# pcb6.net
KiCad netlist of a schematic drawn in EAGLE
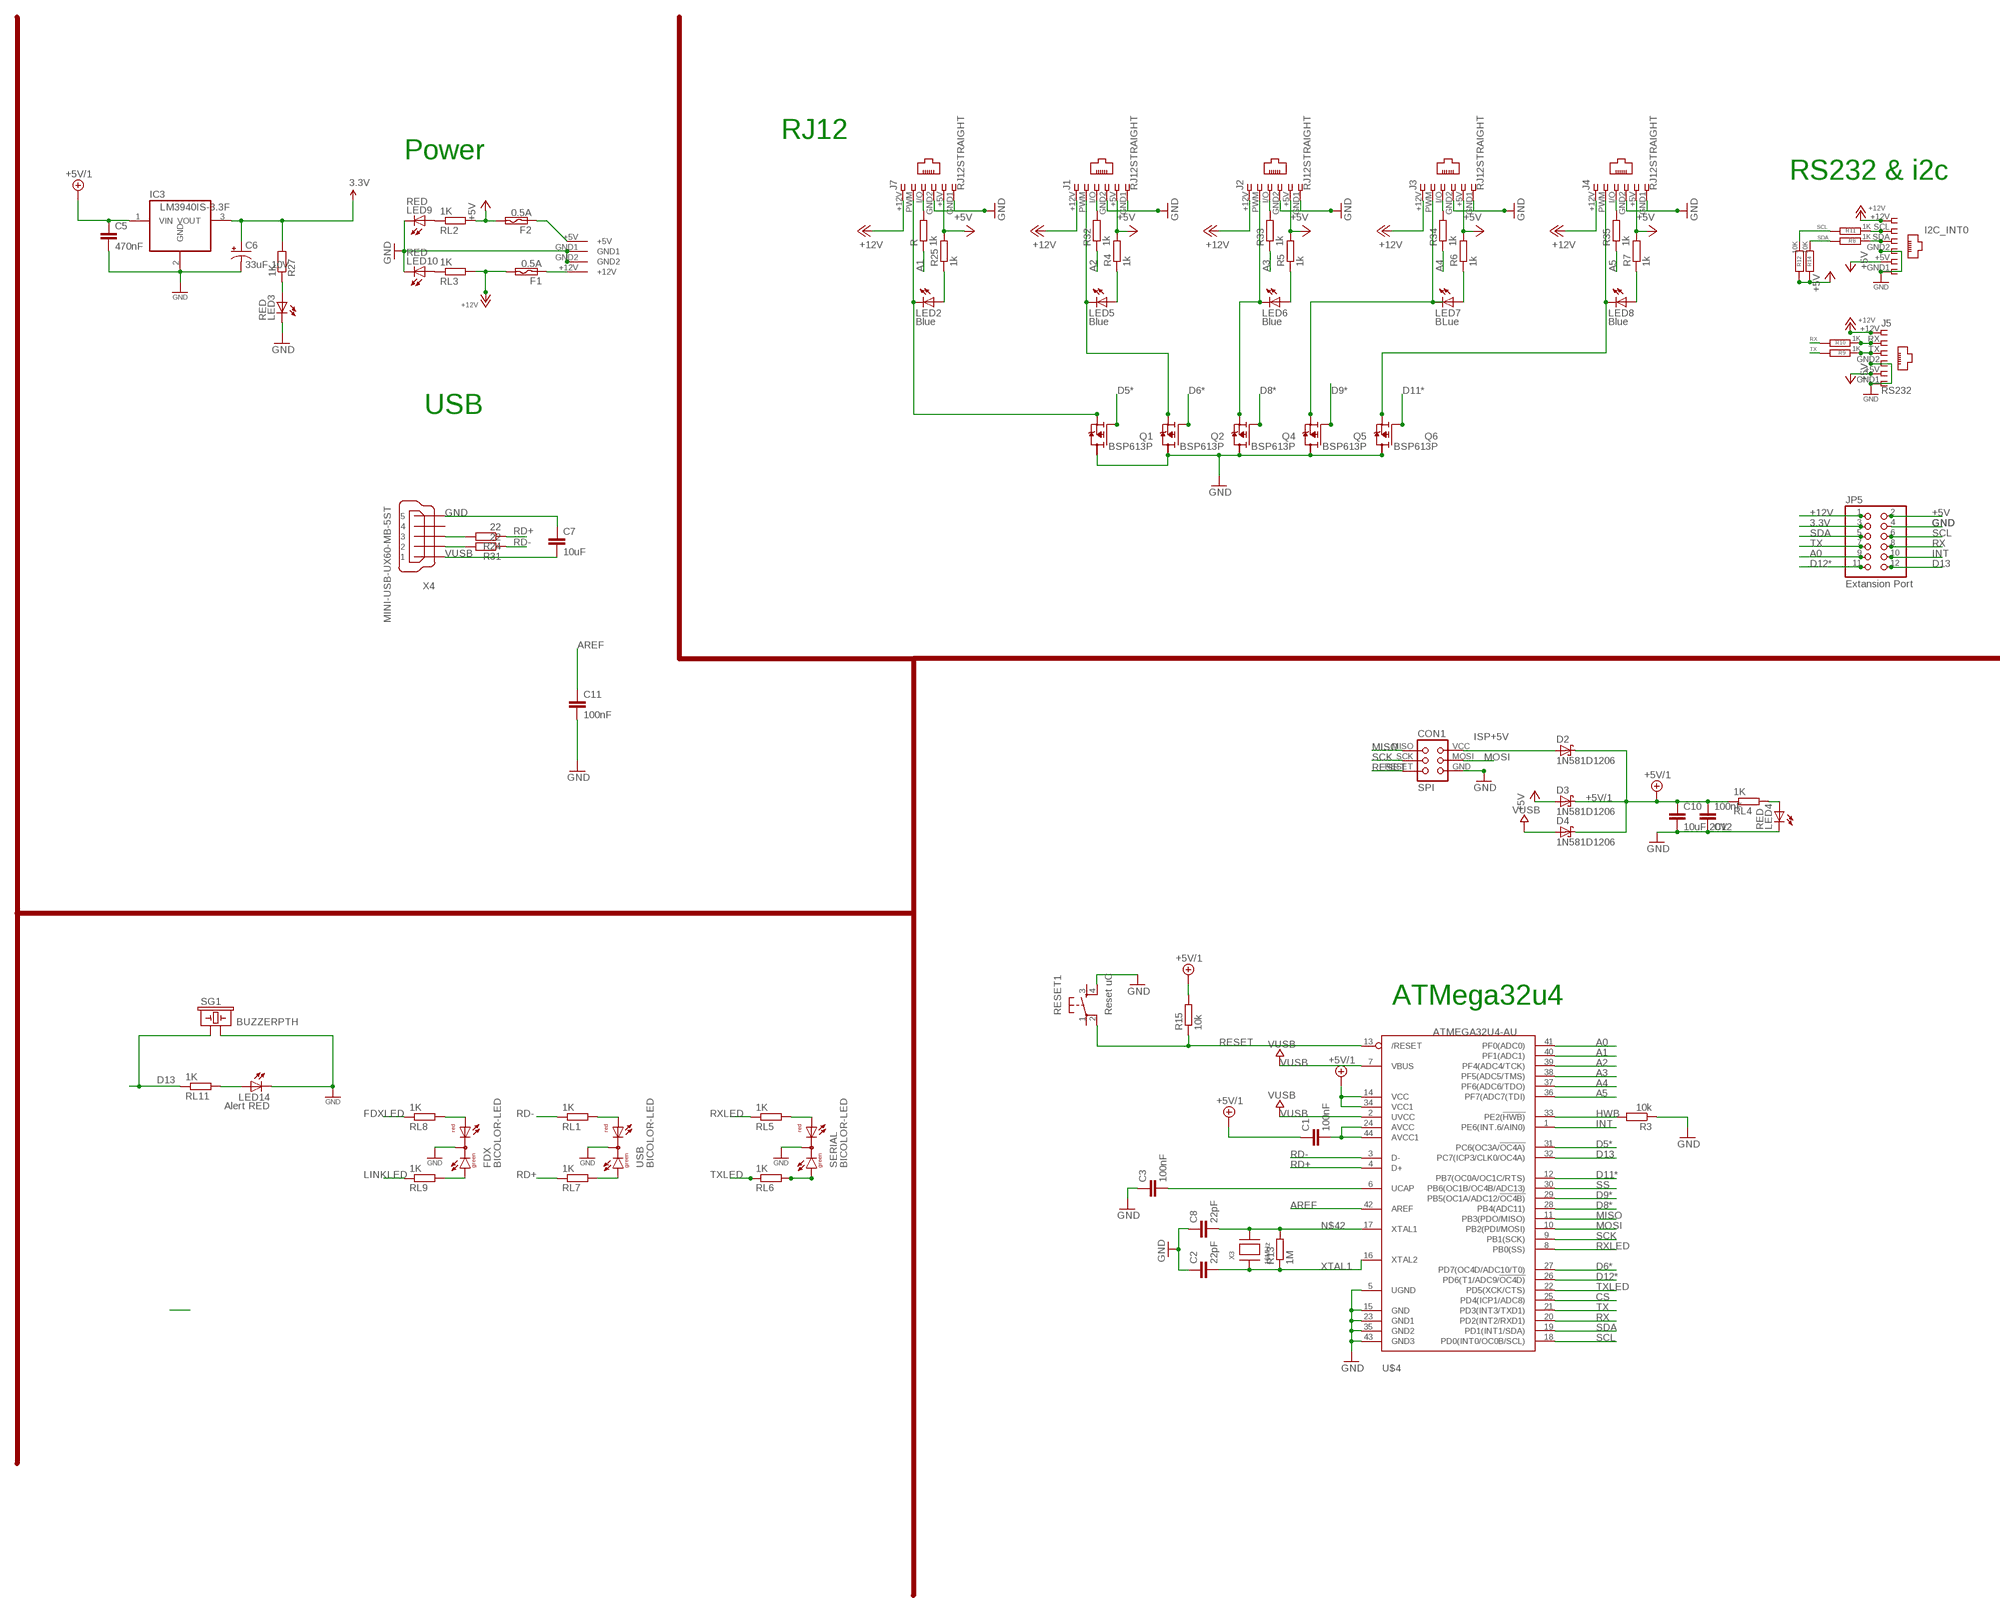
[diagram p0: schematic, sheet 1, part 1 of 2]
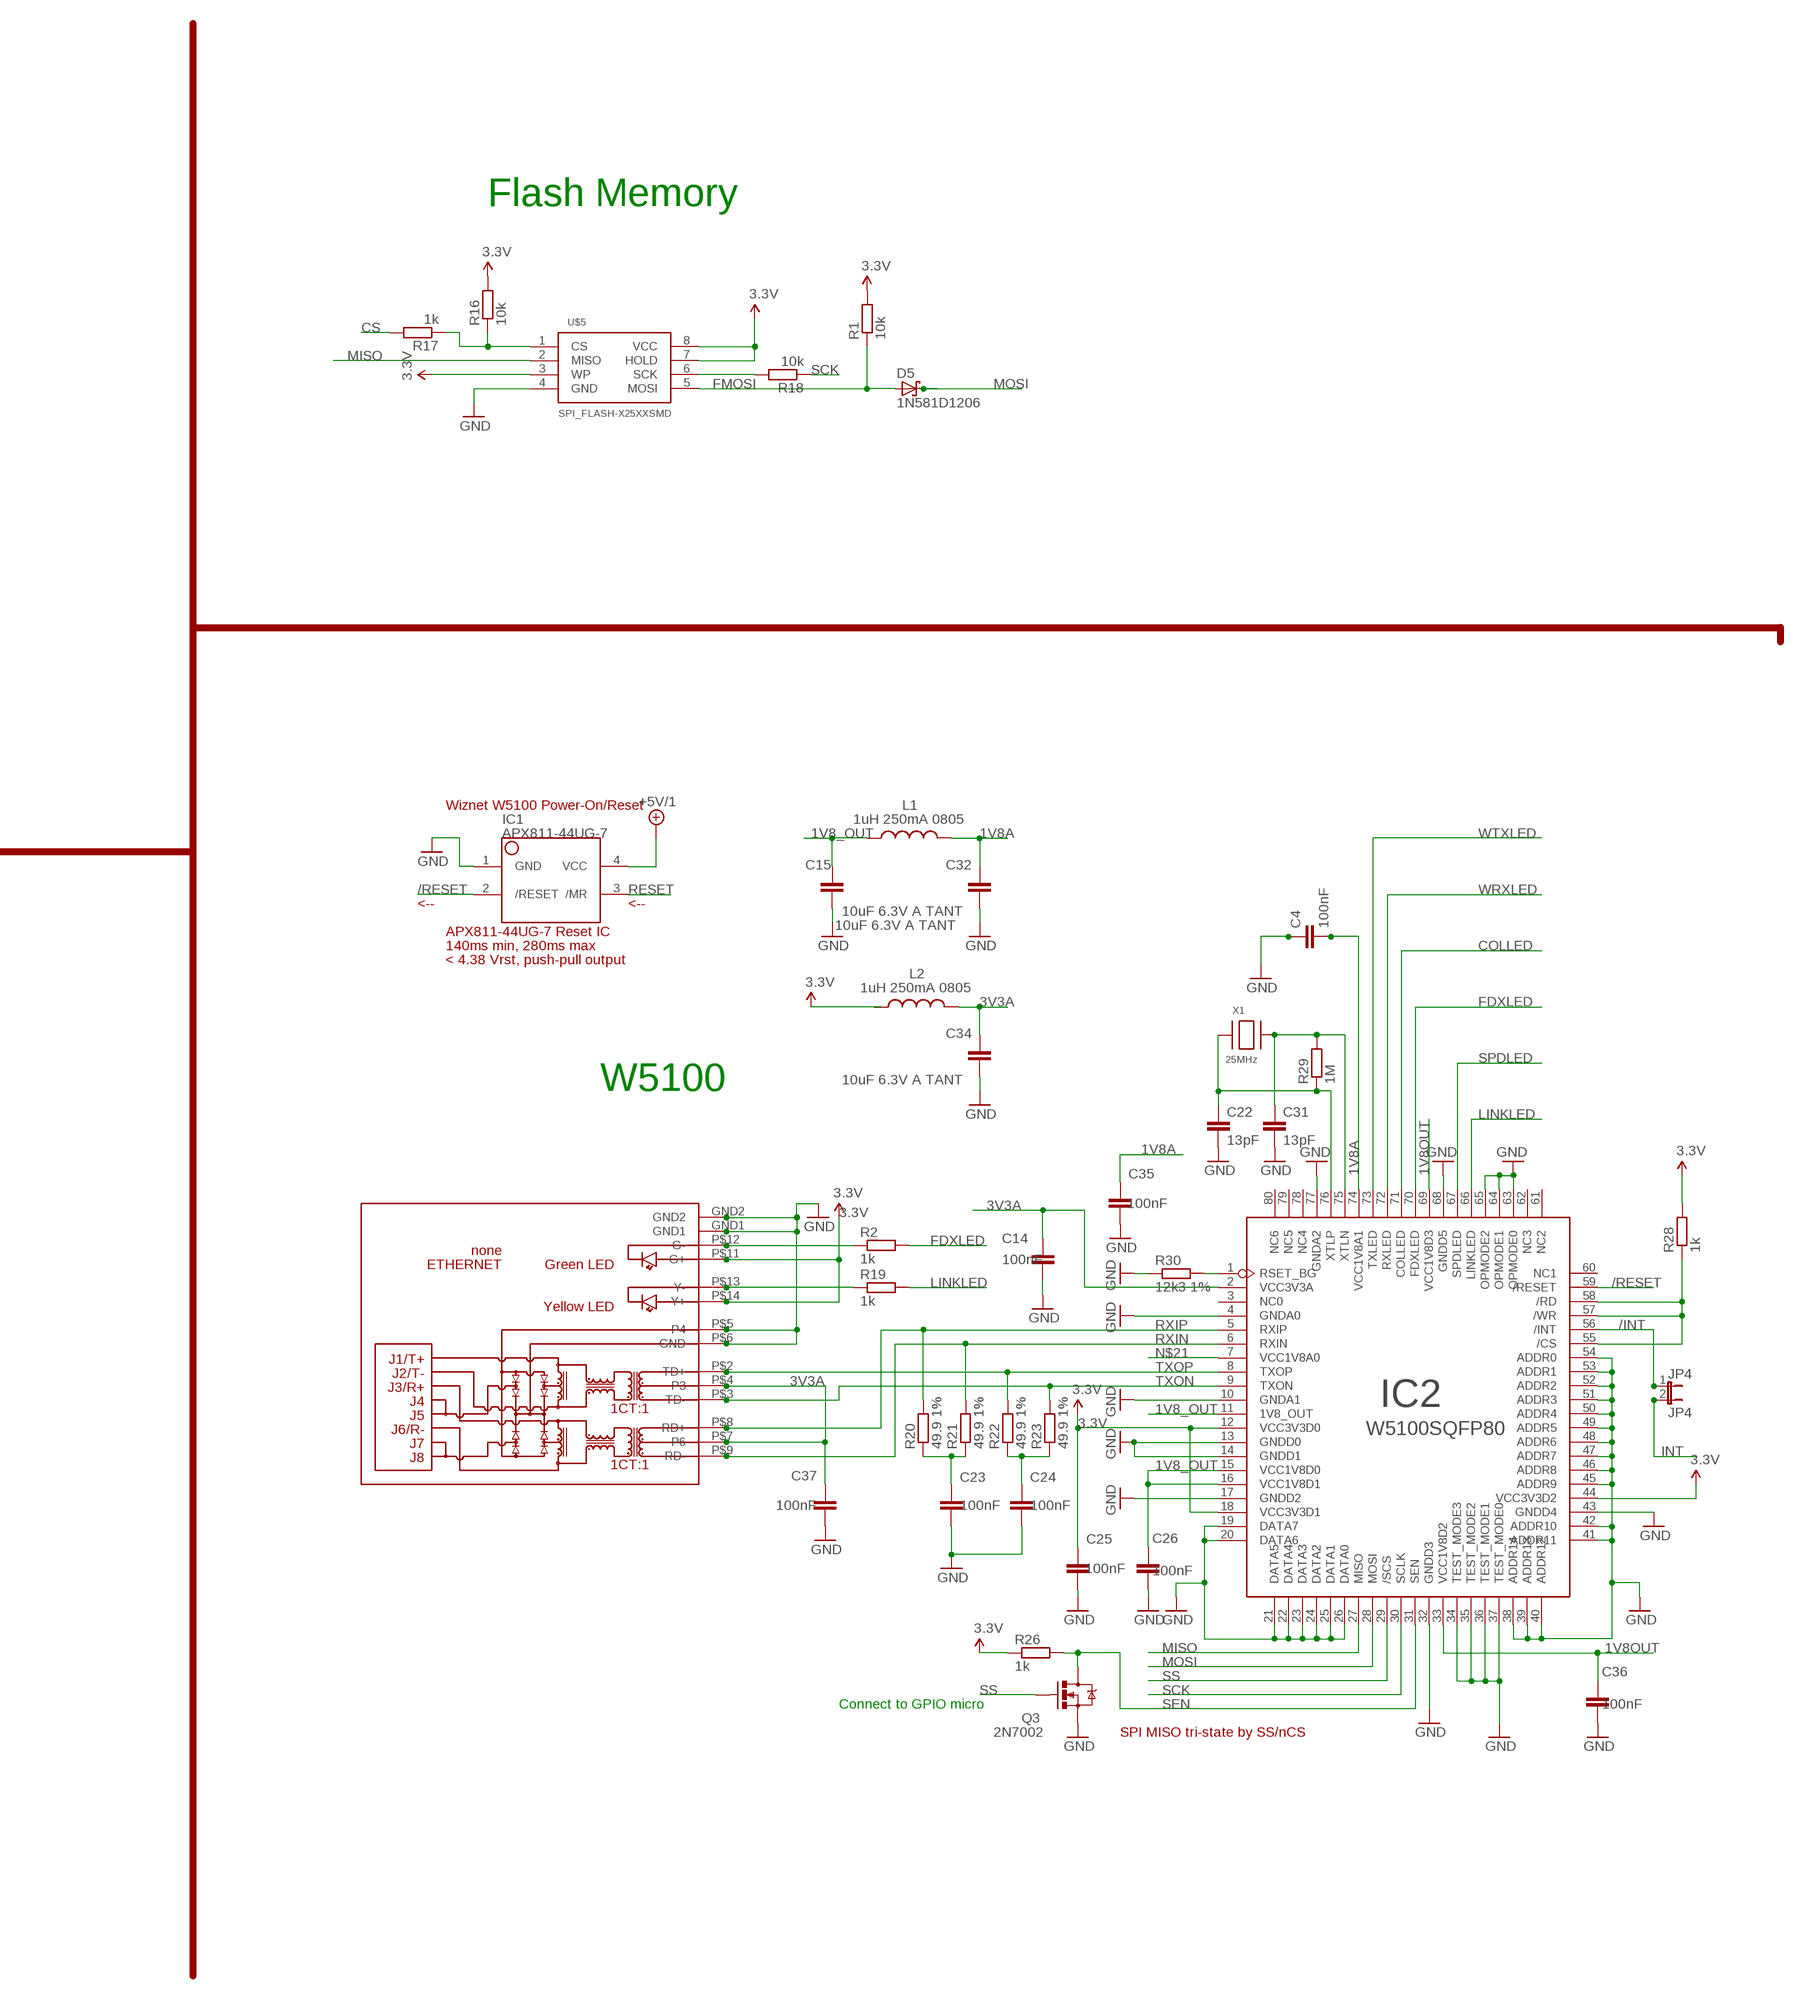
[diagram p1: schematic, sheet 1, part 2 of 2]

(export (version "E")
  (design (tool "Eeschema 10.0.6"))
  (components
    (comp (ref "C1")
      (value "100nF")
      (footprint "eagle-import:C1206")
      (libsource (lib "eagle-import") (part "C-EUC1206"))
    )
    (comp (ref "C2")
      (value "22pF")
      (footprint "eagle-import:C1206")
      (libsource (lib "eagle-import") (part "C-EUC1206"))
    )
    (comp (ref "C3")
      (value "100nF")
      (footprint "eagle-import:C1206")
      (libsource (lib "eagle-import") (part "C-EUC1206"))
    )
    (comp (ref "C4")
      (value "100nF")
      (footprint "eagle-import:C1206")
      (libsource (lib "eagle-import") (part "C-EUC1206"))
    )
    (comp (ref "C5")
      (value "470nF")
      (footprint "eagle-import:C1206")
      (libsource (lib "eagle-import") (part "C-EUC1206"))
    )
    (comp (ref "C6")
      (value "33uF 10V")
      (footprint "eagle-import:EIA7343")
      (libsource (lib "eagle-import") (part "CAP_POL7343"))
    )
    (comp (ref "C7")
      (value "10uF")
      (footprint "eagle-import:C1206")
      (libsource (lib "eagle-import") (part "C-EUC1206"))
    )
    (comp (ref "C8")
      (value "22pF")
      (footprint "eagle-import:C1206")
      (libsource (lib "eagle-import") (part "C-EUC1206"))
    )
    (comp (ref "C10")
      (value "10uF 20V")
      (footprint "eagle-import:C1206")
      (libsource (lib "eagle-import") (part "C-EUC1206"))
    )
    (comp (ref "C11")
      (value "100nF")
      (footprint "eagle-import:C1206")
      (libsource (lib "eagle-import") (part "C-EUC1206"))
    )
    (comp (ref "C12")
      (value "100nF")
      (footprint "eagle-import:C1206")
      (libsource (lib "eagle-import") (part "C-EUC1206"))
    )
    (comp (ref "C14")
      (value "100nF")
      (footprint "eagle-import:C1206")
      (libsource (lib "eagle-import") (part "C-EUC1206"))
    )
    (comp (ref "C15")
      (value "10uF 6.3V A TANT")
      (footprint "eagle-import:C1206")
      (libsource (lib "eagle-import") (part "C-EUC1206"))
    )
    (comp (ref "C22")
      (value "13pF")
      (footprint "eagle-import:C1206")
      (libsource (lib "eagle-import") (part "C-EUC1206"))
    )
    (comp (ref "C23")
      (value "100nF")
      (footprint "eagle-import:C1206")
      (libsource (lib "eagle-import") (part "C-EUC1206"))
    )
    (comp (ref "C24")
      (value "100nF")
      (footprint "eagle-import:C1206")
      (libsource (lib "eagle-import") (part "C-EUC1206"))
    )
    (comp (ref "C25")
      (value "100nF")
      (footprint "eagle-import:C1206")
      (libsource (lib "eagle-import") (part "C-EUC1206"))
    )
    (comp (ref "C26")
      (value "100nF")
      (footprint "eagle-import:C1206")
      (libsource (lib "eagle-import") (part "C-EUC1206"))
    )
    (comp (ref "C31")
      (value "13pF")
      (footprint "eagle-import:C1206")
      (libsource (lib "eagle-import") (part "C-EUC1206"))
    )
    (comp (ref "C32")
      (value "10uF 6.3V A TANT")
      (footprint "eagle-import:C1206")
      (libsource (lib "eagle-import") (part "C-EUC1206"))
    )
    (comp (ref "C34")
      (value "10uF 6.3V A TANT")
      (footprint "eagle-import:C1206")
      (libsource (lib "eagle-import") (part "C-EUC1206"))
    )
    (comp (ref "C35")
      (value "100nF")
      (footprint "eagle-import:C1206")
      (libsource (lib "eagle-import") (part "C-EUC1206"))
    )
    (comp (ref "C36")
      (value "100nF")
      (footprint "eagle-import:C1206")
      (libsource (lib "eagle-import") (part "C-EUC1206"))
    )
    (comp (ref "C37")
      (value "100nF")
      (footprint "eagle-import:C1206")
      (libsource (lib "eagle-import") (part "C-EUC1206"))
    )
    (comp (ref "CON1")
      (value "SPI")
      (footprint "eagle-import:TINYISP")
      (libsource (lib "eagle-import") (part "TINYISP"))
    )
    (comp (ref "D2")
      (value "1N581D1206")
      (footprint "eagle-import:LED-1206")
      (libsource (lib "eagle-import") (part "1N581D1206"))
    )
    (comp (ref "D3")
      (value "1N581D1206")
      (footprint "eagle-import:LED-1206")
      (libsource (lib "eagle-import") (part "1N581D1206"))
    )
    (comp (ref "D4")
      (value "1N581D1206")
      (footprint "eagle-import:LED-1206")
      (libsource (lib "eagle-import") (part "1N581D1206"))
    )
    (comp (ref "D5")
      (value "1N581D1206")
      (footprint "eagle-import:LED-1206")
      (libsource (lib "eagle-import") (part "1N581D1206"))
    )
    (comp (ref "ETHERNET")
      (value "none")
      (footprint "eagle-import:HY931147C")
      (libsource (lib "eagle-import") (part "HY911103AHY911103A"))
    )
    (comp (ref "F1")
      (value "0.5A")
      (footprint "eagle-import:C1812")
      (libsource (lib "eagle-import") (part "POLYSWITCHSMD1812"))
    )
    (comp (ref "F2")
      (value "0.5A")
      (footprint "eagle-import:C1812")
      (libsource (lib "eagle-import") (part "POLYSWITCHSMD1812"))
    )
    (comp (ref "FDX")
      (value "BICOLOR-LED")
      (footprint "eagle-import:BICOLOR-3MM")
      (libsource (lib "eagle-import") (part "BICOLOR-LED"))
    )
    (comp (ref "I2C_INT0")
      (value "I2C")
      (footprint "eagle-import:RJ12-STRAIGHT-I2C")
      (libsource (lib "eagle-import") (part "RJ12STRAIGHT-I2C"))
    )
    (comp (ref "IC1")
      (value "APX811-44UG-7")
      (footprint "eagle-import:SOT143-R")
      (libsource (lib "eagle-import") (part "APX81X-RESET-IC"))
    )
    (comp (ref "IC2")
      (value "W5100SQFP80")
      (footprint "eagle-import:SQFP80")
      (libsource (lib "eagle-import") (part "W5100SQFP80"))
    )
    (comp (ref "IC3")
      (value "LM3940IS-3.3F")
      (footprint "eagle-import:DD-3")
      (fields (field (name "MF") "TEXAS INSTRUMENTS") (field (name "MPN") "REG1117FAKTTT"))
      (libsource (lib "eagle-import") (part "LM3940IS-3.3F"))
    )
    (comp (ref "J1")
      (value "RJ12STRAIGHT")
      (footprint "eagle-import:RJ12-STRAIGHT")
      (libsource (lib "eagle-import") (part "RJ12STRAIGHT"))
    )
    (comp (ref "J2")
      (value "RJ12STRAIGHT")
      (footprint "eagle-import:RJ12-STRAIGHT")
      (libsource (lib "eagle-import") (part "RJ12STRAIGHT"))
    )
    (comp (ref "J3")
      (value "RJ12STRAIGHT")
      (footprint "eagle-import:RJ12-STRAIGHT")
      (libsource (lib "eagle-import") (part "RJ12STRAIGHT"))
    )
    (comp (ref "J4")
      (value "RJ12STRAIGHT")
      (footprint "eagle-import:RJ12-STRAIGHT")
      (libsource (lib "eagle-import") (part "RJ12STRAIGHT"))
    )
    (comp (ref "J5")
      (value "RS232")
      (footprint "eagle-import:RJ12-STRAIGHT-RS232")
      (libsource (lib "eagle-import") (part "RJ12STRAIGHT-RS232-SERVER"))
    )
    (comp (ref "J7")
      (value "RJ12STRAIGHT")
      (footprint "eagle-import:RJ12-STRAIGHT")
      (libsource (lib "eagle-import") (part "RJ12STRAIGHT"))
    )
    (comp (ref "JP4")
      (value "JP4")
      (footprint "eagle-import:1X02")
      (libsource (lib "eagle-import") (part "JUMPER-2PTH"))
    )
    (comp (ref "JP5")
      (value "Extansion Port")
      (footprint "eagle-import:2X06")
      (libsource (lib "eagle-import") (part "PINHD-2X6"))
    )
    (comp (ref "L1")
      (value "1uH 250mA 0805")
      (footprint "eagle-import:L2012C")
      (libsource (lib "eagle-import") (part "L-USL2012C"))
    )
    (comp (ref "L2")
      (value "1uH 250mA 0805")
      (footprint "eagle-import:L2012C")
      (libsource (lib "eagle-import") (part "L-USL2012C"))
    )
    (comp (ref "LED2")
      (value "Blue")
      (footprint "eagle-import:LED3MM")
      (libsource (lib "eagle-import") (part "LED3MM"))
    )
    (comp (ref "LED3")
      (value "RED")
      (footprint "eagle-import:LED3MM")
      (libsource (lib "eagle-import") (part "LED3MM"))
    )
    (comp (ref "LED4")
      (value "RED")
      (footprint "eagle-import:LED3MM")
      (libsource (lib "eagle-import") (part "LED3MM"))
    )
    (comp (ref "LED5")
      (value "Blue")
      (footprint "eagle-import:LED3MM")
      (libsource (lib "eagle-import") (part "LED3MM"))
    )
    (comp (ref "LED6")
      (value "Blue")
      (footprint "eagle-import:LED3MM")
      (libsource (lib "eagle-import") (part "LED3MM"))
    )
    (comp (ref "LED7")
      (value "BLue")
      (footprint "eagle-import:LED3MM")
      (libsource (lib "eagle-import") (part "LED3MM"))
    )
    (comp (ref "LED8")
      (value "Blue")
      (footprint "eagle-import:LED3MM")
      (libsource (lib "eagle-import") (part "LED3MM"))
    )
    (comp (ref "LED9")
      (value "RED")
      (footprint "eagle-import:LED3MM")
      (libsource (lib "eagle-import") (part "LED3MM"))
    )
    (comp (ref "LED10")
      (value "RED")
      (footprint "eagle-import:LED3MM")
      (libsource (lib "eagle-import") (part "LED3MM"))
    )
    (comp (ref "LED14")
      (value "Alert RED")
      (footprint "eagle-import:LED3MM")
      (libsource (lib "eagle-import") (part "LED3MM"))
    )
    (comp (ref "Q1")
      (value "BSP613P")
      (footprint "eagle-import:PG-SOT-223")
      (libsource (lib "eagle-import") (part "BSP613P"))
    )
    (comp (ref "Q2")
      (value "BSP613P")
      (footprint "eagle-import:PG-SOT-223")
      (libsource (lib "eagle-import") (part "BSP613P"))
    )
    (comp (ref "Q3")
      (value "2N7002")
      (footprint "eagle-import:SOT23-3")
      (libsource (lib "eagle-import") (part "MOSFET-NCHANNELSMD"))
    )
    (comp (ref "Q4")
      (value "BSP613P")
      (footprint "eagle-import:PG-SOT-223")
      (libsource (lib "eagle-import") (part "BSP613P"))
    )
    (comp (ref "Q5")
      (value "BSP613P")
      (footprint "eagle-import:PG-SOT-223")
      (libsource (lib "eagle-import") (part "BSP613P"))
    )
    (comp (ref "Q6")
      (value "BSP613P")
      (footprint "eagle-import:PG-SOT-223")
      (libsource (lib "eagle-import") (part "BSP613P"))
    )
    (comp (ref "R")
      (value "1k")
      (footprint "eagle-import:R0805")
      (libsource (lib "eagle-import") (part "R-EU_R0805"))
    )
    (comp (ref "R1")
      (value "10k")
      (footprint "eagle-import:R1206")
      (libsource (lib "eagle-import") (part "R-EU_R1206"))
    )
    (comp (ref "R2")
      (value "1k")
      (footprint "eagle-import:R0805")
      (libsource (lib "eagle-import") (part "R-EU_R0805"))
    )
    (comp (ref "R3")
      (value "10k")
      (footprint "eagle-import:R1206")
      (libsource (lib "eagle-import") (part "R-EU_R1206"))
    )
    (comp (ref "R4")
      (value "1k")
      (footprint "eagle-import:R0805")
      (libsource (lib "eagle-import") (part "R-EU_R0805"))
    )
    (comp (ref "R5")
      (value "1k")
      (footprint "eagle-import:R0805")
      (libsource (lib "eagle-import") (part "R-EU_R0805"))
    )
    (comp (ref "R6")
      (value "1k")
      (footprint "eagle-import:R0805")
      (libsource (lib "eagle-import") (part "R-EU_R0805"))
    )
    (comp (ref "R7")
      (value "1k")
      (footprint "eagle-import:R0805")
      (libsource (lib "eagle-import") (part "R-EU_R0805"))
    )
    (comp (ref "R8")
      (value "1K")
      (footprint "eagle-import:R0805")
      (libsource (lib "eagle-import") (part "R-EU_R0805"))
    )
    (comp (ref "R9")
      (value "1K")
      (footprint "eagle-import:R0805")
      (libsource (lib "eagle-import") (part "R-EU_R0805"))
    )
    (comp (ref "R10")
      (value "1K")
      (footprint "eagle-import:R0805")
      (libsource (lib "eagle-import") (part "R-EU_R0805"))
    )
    (comp (ref "R11")
      (value "1K")
      (footprint "eagle-import:R0805")
      (libsource (lib "eagle-import") (part "R-EU_R0805"))
    )
    (comp (ref "R12")
      (value "10K")
      (footprint "eagle-import:R1206")
      (libsource (lib "eagle-import") (part "R-EU_R1206"))
    )
    (comp (ref "R13")
      (value "1M")
      (footprint "eagle-import:R1206")
      (libsource (lib "eagle-import") (part "R-EU_R1206"))
    )
    (comp (ref "R14")
      (value "10K")
      (footprint "eagle-import:R1206")
      (libsource (lib "eagle-import") (part "R-EU_R1206"))
    )
    (comp (ref "R15")
      (value "10k")
      (footprint "eagle-import:R1206")
      (libsource (lib "eagle-import") (part "R-EU_R1206"))
    )
    (comp (ref "R16")
      (value "10k")
      (footprint "eagle-import:R1206")
      (libsource (lib "eagle-import") (part "R-EU_R1206"))
    )
    (comp (ref "R17")
      (value "1k")
      (footprint "eagle-import:R0805")
      (libsource (lib "eagle-import") (part "R-EU_R0805"))
    )
    (comp (ref "R18")
      (value "10k")
      (footprint "eagle-import:R1206")
      (libsource (lib "eagle-import") (part "R-EU_R1206"))
    )
    (comp (ref "R19")
      (value "1k")
      (footprint "eagle-import:R0805")
      (libsource (lib "eagle-import") (part "R-EU_R0805"))
    )
    (comp (ref "R20")
      (value "49.9 1%")
      (footprint "eagle-import:R0805W")
      (libsource (lib "eagle-import") (part "R-EU_R0805W"))
    )
    (comp (ref "R21")
      (value "49.9 1%")
      (footprint "eagle-import:R0805W")
      (libsource (lib "eagle-import") (part "R-EU_R0805W"))
    )
    (comp (ref "R22")
      (value "49.9 1%")
      (footprint "eagle-import:R0805W")
      (libsource (lib "eagle-import") (part "R-EU_R0805W"))
    )
    (comp (ref "R23")
      (value "49.9 1%")
      (footprint "eagle-import:R0805W")
      (libsource (lib "eagle-import") (part "R-EU_R0805W"))
    )
    (comp (ref "R24")
      (value "22")
      (footprint "eagle-import:M1206")
      (libsource (lib "eagle-import") (part "resistor_R-EU_M1206"))
    )
    (comp (ref "R25")
      (value "1k")
      (footprint "eagle-import:R0805")
      (libsource (lib "eagle-import") (part "R-EU_R0805"))
    )
    (comp (ref "R26")
      (value "1k")
      (footprint "eagle-import:R0805")
      (libsource (lib "eagle-import") (part "R-EU_R0805"))
    )
    (comp (ref "R27")
      (value "1K")
      (footprint "eagle-import:R0805")
      (libsource (lib "eagle-import") (part "R-EU_R0805"))
    )
    (comp (ref "R28")
      (value "1k")
      (footprint "eagle-import:R0805")
      (libsource (lib "eagle-import") (part "R-EU_R0805"))
    )
    (comp (ref "R29")
      (value "1M")
      (footprint "eagle-import:R1206")
      (libsource (lib "eagle-import") (part "R-EU_R1206"))
    )
    (comp (ref "R30")
      (value "12k3 1%")
      (footprint "eagle-import:R0805W")
      (libsource (lib "eagle-import") (part "R-EU_R0805W"))
    )
    (comp (ref "R31")
      (value "22")
      (footprint "eagle-import:M1206")
      (libsource (lib "eagle-import") (part "resistor_R-EU_M1206"))
    )
    (comp (ref "R32")
      (value "1k")
      (footprint "eagle-import:R0805")
      (libsource (lib "eagle-import") (part "R-EU_R0805"))
    )
    (comp (ref "R33")
      (value "1k")
      (footprint "eagle-import:R0805")
      (libsource (lib "eagle-import") (part "R-EU_R0805"))
    )
    (comp (ref "R34")
      (value "1k")
      (footprint "eagle-import:R0805")
      (libsource (lib "eagle-import") (part "R-EU_R0805"))
    )
    (comp (ref "R35")
      (value "1k")
      (footprint "eagle-import:R0805")
      (libsource (lib "eagle-import") (part "R-EU_R0805"))
    )
    (comp (ref "RESET1")
      (value "Reset uC")
      (footprint "eagle-import:TACTILE_SWITCH_SMD")
      (libsource (lib "eagle-import") (part "TAC_SWITCHSMD"))
    )
    (comp (ref "RL1")
      (value "1K")
      (footprint "eagle-import:R0805")
      (libsource (lib "eagle-import") (part "R-EU_R0805"))
    )
    (comp (ref "RL2")
      (value "1K")
      (footprint "eagle-import:R0805")
      (libsource (lib "eagle-import") (part "R-EU_R0805"))
    )
    (comp (ref "RL3")
      (value "1K")
      (footprint "eagle-import:R0805")
      (libsource (lib "eagle-import") (part "R-EU_R0805"))
    )
    (comp (ref "RL4")
      (value "1K")
      (footprint "eagle-import:R0805@1")
      (libsource (lib "eagle-import") (part "resistor_R-EU_R0805"))
    )
    (comp (ref "RL5")
      (value "1K")
      (footprint "eagle-import:R0805")
      (libsource (lib "eagle-import") (part "R-EU_R0805"))
    )
    (comp (ref "RL6")
      (value "1K")
      (footprint "eagle-import:R0805")
      (libsource (lib "eagle-import") (part "R-EU_R0805"))
    )
    (comp (ref "RL7")
      (value "1K")
      (footprint "eagle-import:R0805")
      (libsource (lib "eagle-import") (part "R-EU_R0805"))
    )
    (comp (ref "RL8")
      (value "1K")
      (footprint "eagle-import:R0805")
      (libsource (lib "eagle-import") (part "R-EU_R0805"))
    )
    (comp (ref "RL9")
      (value "1K")
      (footprint "eagle-import:R0805")
      (libsource (lib "eagle-import") (part "R-EU_R0805"))
    )
    (comp (ref "RL11")
      (value "1K")
      (footprint "eagle-import:R0805")
      (libsource (lib "eagle-import") (part "R-EU_R0805"))
    )
    (comp (ref "SERIAL")
      (value "BICOLOR-LED")
      (footprint "eagle-import:BICOLOR-3MM")
      (libsource (lib "eagle-import") (part "BICOLOR-LED"))
    )
    (comp (ref "SG1")
      (value "BUZZERPTH")
      (footprint "eagle-import:BUZZER-12MM")
      (libsource (lib "eagle-import") (part "BUZZERPTH"))
    )
    (comp (ref "U$4")
      (value "ATMEGA32U4-AU")
      (footprint "eagle-import:TQFP44")
      (libsource (lib "eagle-import") (part "ATMEGA32U4-AU"))
    )
    (comp (ref "U$5")
      (value "SPI_FLASH-X25XXSMD")
      (footprint "eagle-import:SO08")
      (libsource (lib "eagle-import") (part "SPI_FLASH-X25XXSMD"))
    )
    (comp (ref "U$6")
      (value "KPJX-4S-S")
      (footprint "eagle-import:KPJX-4S-S")
      (libsource (lib "eagle-import") (part "KPJX-4S-S"))
    )
    (comp (ref "USB")
      (value "BICOLOR-LED")
      (footprint "eagle-import:BICOLOR-3MM")
      (libsource (lib "eagle-import") (part "BICOLOR-LED"))
    )
    (comp (ref "X1")
      (value "25MHz")
      (footprint "eagle-import:NX6035")
      (libsource (lib "eagle-import") (part "XTALNX6035"))
    )
    (comp (ref "X3")
      (value "16MHz")
      (footprint "eagle-import:NX6035")
      (libsource (lib "eagle-import") (part "XTALNX6035"))
    )
    (comp (ref "X4")
      (value "MINI-USB-UX60-MB-5ST")
      (footprint "eagle-import:UX60-MB-5ST")
      (libsource (lib "eagle-import") (part "MINI-USB-UX60-MB-5ST"))
    )
  )
  (nets
    (net (code "1") (name "+5V") (class "Default")
      (node (ref "D3") (pin "A") (pinfunction "A_A") (pintype "passive"))
      (node (ref "F2") (pin "2") (pinfunction "2_2") (pintype "passive"))
      (node (ref "I2C_INT0") (pin "+5V") (pinfunction "5_+5V") (pintype "power_in"))
      (node (ref "J1") (pin "+5V") (pinfunction "5_+5V") (pintype "power_in"))
      (node (ref "J2") (pin "+5V") (pinfunction "5_+5V") (pintype "power_in"))
      (node (ref "J3") (pin "+5V") (pinfunction "5_+5V") (pintype "power_in"))
      (node (ref "J4") (pin "+5V") (pinfunction "5_+5V") (pintype "power_in"))
      (node (ref "J5") (pin "+5V") (pinfunction "5_+5V") (pintype "power_in"))
      (node (ref "J7") (pin "+5V") (pinfunction "5_+5V") (pintype "power_in"))
      (node (ref "JP5") (pin "2") (pinfunction "2_2") (pintype "passive"))
      (node (ref "R12") (pin "2") (pinfunction "2_2") (pintype "passive"))
      (node (ref "R14") (pin "2") (pinfunction "2_2") (pintype "passive"))
      (node (ref "R25") (pin "2") (pinfunction "2_2") (pintype "passive"))
      (node (ref "R4") (pin "2") (pinfunction "2_2") (pintype "passive"))
      (node (ref "R5") (pin "2") (pinfunction "2_2") (pintype "passive"))
      (node (ref "R6") (pin "2") (pinfunction "2_2") (pintype "passive"))
      (node (ref "R7") (pin "2") (pinfunction "2_2") (pintype "passive"))
      (node (ref "RL2") (pin "2") (pinfunction "2_2") (pintype "passive"))
    )
    (net (code "2") (name "+5V{slash}1") (class "Default")
      (node (ref "C1") (pin "1") (pinfunction "1_1") (pintype "passive"))
      (node (ref "C10") (pin "1") (pinfunction "1_1") (pintype "passive"))
      (node (ref "C12") (pin "2") (pinfunction "2_2") (pintype "passive"))
      (node (ref "C5") (pin "1") (pinfunction "1_1") (pintype "passive"))
      (node (ref "D2") (pin "C") (pinfunction "C_C") (pintype "passive"))
      (node (ref "D3") (pin "C") (pinfunction "C_C") (pintype "passive"))
      (node (ref "D4") (pin "C") (pinfunction "C_C") (pintype "passive"))
      (node (ref "IC1") (pin "4") (pinfunction "VCC_4") (pintype "power_in"))
      (node (ref "IC3") (pin "1") (pinfunction "VIN_1") (pintype "input"))
      (node (ref "R15") (pin "2") (pinfunction "2_2") (pintype "passive"))
      (node (ref "RL4") (pin "1") (pinfunction "1_1") (pintype "passive"))
      (node (ref "U$4") (pin "14") (pinfunction "VCC_14") (pintype "bidirectional"))
      (node (ref "U$4") (pin "34") (pinfunction "VCC1_34") (pintype "bidirectional"))
    )
    (net (code "3") (name "+12V") (class "Default")
      (node (ref "F1") (pin "2") (pinfunction "2_2") (pintype "passive"))
      (node (ref "I2C_INT0") (pin "+12V") (pinfunction "1_+12V") (pintype "power_in"))
      (node (ref "J1") (pin "+12V") (pinfunction "1_+12V") (pintype "power_in"))
      (node (ref "J2") (pin "+12V") (pinfunction "1_+12V") (pintype "power_in"))
      (node (ref "J3") (pin "+12V") (pinfunction "1_+12V") (pintype "power_in"))
      (node (ref "J4") (pin "+12V") (pinfunction "1_+12V") (pintype "power_in"))
      (node (ref "J5") (pin "+12V") (pinfunction "1_+12V") (pintype "power_in"))
      (node (ref "J7") (pin "+12V") (pinfunction "1_+12V") (pintype "power_in"))
      (node (ref "JP5") (pin "1") (pinfunction "1_1") (pintype "passive"))
      (node (ref "RL3") (pin "2") (pinfunction "2_2") (pintype "passive"))
    )
    (net (code "4") (name "/1V8A") (class "Default")
      (node (ref "C32") (pin "1") (pinfunction "1_1") (pintype "passive"))
      (node (ref "C35") (pin "1") (pinfunction "1_1") (pintype "passive"))
      (node (ref "C4") (pin "2") (pinfunction "2_2") (pintype "passive"))
      (node (ref "IC2") (pin "74") (pinfunction "VCC1V8A1_74") (pintype "bidirectional"))
      (node (ref "L1") (pin "2") (pinfunction "2_2") (pintype "passive"))
    )
    (net (code "5") (name "/1V8OUT") (class "Default")
      (node (ref "C36") (pin "1") (pinfunction "1_1") (pintype "passive"))
      (node (ref "IC2") (pin "33") (pinfunction "VCC1V8D2_33") (pintype "bidirectional"))
      (node (ref "IC2") (pin "69") (pinfunction "VCC1V8D3_69") (pintype "bidirectional"))
    )
    (net (code "6") (name "/1V8_OUT") (class "Default")
      (node (ref "C15") (pin "1") (pinfunction "1_1") (pintype "passive"))
      (node (ref "C26") (pin "1") (pinfunction "1_1") (pintype "passive"))
      (node (ref "IC2") (pin "11") (pinfunction "1V8_OUT_11") (pintype "bidirectional"))
      (node (ref "IC2") (pin "15") (pinfunction "VCC1V8D0_15") (pintype "bidirectional"))
      (node (ref "IC2") (pin "16") (pinfunction "VCC1V8D1_16") (pintype "bidirectional"))
      (node (ref "L1") (pin "1") (pinfunction "1_1") (pintype "passive"))
    )
    (net (code "7") (name "/3V3A") (class "Default")
      (node (ref "C14") (pin "1") (pinfunction "1_1") (pintype "passive"))
      (node (ref "C34") (pin "1") (pinfunction "1_1") (pintype "passive"))
      (node (ref "C37") (pin "1") (pinfunction "1_1") (pintype "passive"))
      (node (ref "ETHERNET") (pin "P$4") (pinfunction "P3_P$4") (pintype "bidirectional"))
      (node (ref "ETHERNET") (pin "P$7") (pinfunction "P6_P$7") (pintype "bidirectional"))
      (node (ref "IC2") (pin "2") (pinfunction "VCC3V3A_2") (pintype "bidirectional"))
      (node (ref "L2") (pin "2") (pinfunction "2_2") (pintype "passive"))
    )
    (net (code "8") (name "/A0") (class "Default")
      (node (ref "JP5") (pin "9") (pinfunction "9_9") (pintype "passive"))
      (node (ref "U$4") (pin "41") (pinfunction "PF0(ADC0)_41") (pintype "bidirectional"))
    )
    (net (code "9") (name "/A1") (class "Default")
      (node (ref "R") (pin "1") (pinfunction "1_1") (pintype "passive"))
      (node (ref "U$4") (pin "40") (pinfunction "PF1(ADC1)_40") (pintype "bidirectional"))
    )
    (net (code "10") (name "/A2") (class "Default")
      (node (ref "R32") (pin "1") (pinfunction "1_1") (pintype "passive"))
      (node (ref "U$4") (pin "39") (pinfunction "PF4(ADC4/TCK)_39") (pintype "bidirectional"))
    )
    (net (code "11") (name "/A3") (class "Default")
      (node (ref "R33") (pin "1") (pinfunction "1_1") (pintype "passive"))
      (node (ref "U$4") (pin "38") (pinfunction "PF5(ADC5/TMS)_38") (pintype "bidirectional"))
    )
    (net (code "12") (name "/A4") (class "Default")
      (node (ref "R34") (pin "1") (pinfunction "1_1") (pintype "passive"))
      (node (ref "U$4") (pin "37") (pinfunction "PF6(ADC6/TDO)_37") (pintype "bidirectional"))
    )
    (net (code "13") (name "/A5") (class "Default")
      (node (ref "R35") (pin "1") (pinfunction "1_1") (pintype "passive"))
      (node (ref "U$4") (pin "36") (pinfunction "PF7(ADC7(TDI)_36") (pintype "bidirectional"))
    )
    (net (code "14") (name "/AREF") (class "Default")
      (node (ref "C11") (pin "1") (pinfunction "1_1") (pintype "passive"))
      (node (ref "U$4") (pin "42") (pinfunction "AREF_42") (pintype "bidirectional"))
    )
    (net (code "15") (name "/COLLED") (class "Default")
      (node (ref "IC2") (pin "71") (pinfunction "COLLED_71") (pintype "bidirectional"))
    )
    (net (code "16") (name "/CS") (class "Default")
      (node (ref "R17") (pin "2") (pinfunction "2_2") (pintype "passive"))
      (node (ref "U$4") (pin "25") (pinfunction "PD4(ICP1/ADC8)_25") (pintype "bidirectional"))
    )
    (net (code "17") (name "/D5*") (class "Default")
      (node (ref "Q1") (pin "1") (pinfunction "G_1") (pintype "passive"))
      (node (ref "U$4") (pin "31") (pinfunction "PC6(OC3A/~{OC4A})_31") (pintype "bidirectional"))
    )
    (net (code "18") (name "/D6*") (class "Default")
      (node (ref "Q2") (pin "1") (pinfunction "G_1") (pintype "passive"))
      (node (ref "U$4") (pin "27") (pinfunction "PD7(OC4D/ADC10/T0)_27") (pintype "bidirectional"))
    )
    (net (code "19") (name "/D8*") (class "Default")
      (node (ref "Q4") (pin "1") (pinfunction "G_1") (pintype "passive"))
      (node (ref "U$4") (pin "28") (pinfunction "PB4(ADC11)_28") (pintype "bidirectional"))
    )
    (net (code "20") (name "/D9*") (class "Default")
      (node (ref "Q5") (pin "1") (pinfunction "G_1") (pintype "passive"))
      (node (ref "U$4") (pin "29") (pinfunction "PB5(OC1A/ADC12/~{OC4B})_29") (pintype "bidirectional"))
    )
    (net (code "21") (name "/D11*") (class "Default")
      (node (ref "Q6") (pin "1") (pinfunction "G_1") (pintype "passive"))
      (node (ref "U$4") (pin "12") (pinfunction "PB7(OC0A/OC1C/RTS)_12") (pintype "bidirectional"))
    )
    (net (code "22") (name "/D12*") (class "Default")
      (node (ref "JP5") (pin "11") (pinfunction "11_11") (pintype "passive"))
      (node (ref "U$4") (pin "26") (pinfunction "PD6(T1/ADC9/~{OC4D})_26") (pintype "bidirectional"))
    )
    (net (code "23") (name "/D13") (class "Default")
      (node (ref "JP5") (pin "12") (pinfunction "12_12") (pintype "passive"))
      (node (ref "RL11") (pin "1") (pinfunction "1_1") (pintype "passive"))
      (node (ref "SG1") (pin "+") (pinfunction "1_+") (pintype "passive"))
      (node (ref "U$4") (pin "32") (pinfunction "PC7(ICP3/CLK0/OC4A)_32") (pintype "bidirectional"))
    )
    (net (code "24") (name "/FDXLED") (class "Default")
      (node (ref "IC2") (pin "70") (pinfunction "FDXLED_70") (pintype "bidirectional"))
      (node (ref "R2") (pin "2") (pinfunction "2_2") (pintype "passive"))
      (node (ref "RL8") (pin "1") (pinfunction "1_1") (pintype "passive"))
    )
    (net (code "25") (name "/FMOSI") (class "Default")
      (node (ref "D5") (pin "A") (pinfunction "A_A") (pintype "passive"))
      (node (ref "R1") (pin "1") (pinfunction "1_1") (pintype "passive"))
      (node (ref "U$5") (pin "5") (pinfunction "MOSI_5") (pintype "bidirectional"))
    )
    (net (code "26") (name "/HWB") (class "Default")
      (node (ref "R3") (pin "2") (pinfunction "2_2") (pintype "passive"))
      (node (ref "U$4") (pin "33") (pinfunction "PE2(~{HWB})_33") (pintype "bidirectional"))
    )
    (net (code "27") (name "/INT") (class "Default")
      (node (ref "JP4") (pin "2") (pinfunction "2_2") (pintype "passive"))
      (node (ref "JP5") (pin "10") (pinfunction "10_10") (pintype "passive"))
      (node (ref "U$4") (pin "1") (pinfunction "PE6(INT.6/AIN0)_1") (pintype "bidirectional"))
    )
    (net (code "28") (name "/ISP+5V") (class "Default")
      (node (ref "CON1") (pin "VCC") (pinfunction "VCC_VCC") (pintype "passive"))
      (node (ref "D2") (pin "A") (pinfunction "A_A") (pintype "passive"))
    )
    (net (code "29") (name "/LINKLED") (class "Default")
      (node (ref "IC2") (pin "66") (pinfunction "LINKLED_66") (pintype "bidirectional"))
      (node (ref "R19") (pin "2") (pinfunction "2_2") (pintype "passive"))
      (node (ref "RL9") (pin "1") (pinfunction "1_1") (pintype "passive"))
    )
    (net (code "30") (name "/MISO") (class "Default")
      (node (ref "CON1") (pin "MISO") (pinfunction "MISO_MISO") (pintype "passive"))
      (node (ref "IC2") (pin "27") (pinfunction "MISO_27") (pintype "bidirectional"))
      (node (ref "U$4") (pin "11") (pinfunction "PB3(PDO/MISO)_11") (pintype "bidirectional"))
      (node (ref "U$5") (pin "2") (pinfunction "MISO_2") (pintype "bidirectional"))
    )
    (net (code "31") (name "/MOSI") (class "Default")
      (node (ref "CON1") (pin "MOSI") (pinfunction "MOSI_MOSI") (pintype "passive"))
      (node (ref "D5") (pin "C") (pinfunction "C_C") (pintype "passive"))
      (node (ref "IC2") (pin "28") (pinfunction "MOSI_28") (pintype "bidirectional"))
      (node (ref "U$4") (pin "10") (pinfunction "PB2(PDI/MOSI)_10") (pintype "bidirectional"))
    )
    (net (code "32") (name "/N$21") (class "Default")
      (node (ref "IC2") (pin "7") (pinfunction "VCC1V8A0_7") (pintype "bidirectional"))
    )
    (net (code "33") (name "/N$42") (class "Default")
      (node (ref "C8") (pin "2") (pinfunction "2_2") (pintype "passive"))
      (node (ref "R13") (pin "2") (pinfunction "2_2") (pintype "passive"))
      (node (ref "U$4") (pin "17") (pinfunction "XTAL1_17") (pintype "bidirectional"))
      (node (ref "X3") (pin "P$2") (pinfunction "P$2_P$2") (pintype "bidirectional"))
    )
    (net (code "34") (name "/RD+") (class "Default")
      (node (ref "R24") (pin "1") (pinfunction "1_1") (pintype "passive"))
      (node (ref "RL7") (pin "1") (pinfunction "1_1") (pintype "passive"))
      (node (ref "U$4") (pin "4") (pinfunction "D+_4") (pintype "bidirectional"))
    )
    (net (code "35") (name "/RD-") (class "Default")
      (node (ref "R31") (pin "1") (pinfunction "1_1") (pintype "passive"))
      (node (ref "RL1") (pin "1") (pinfunction "1_1") (pintype "passive"))
      (node (ref "U$4") (pin "3") (pinfunction "D-_3") (pintype "bidirectional"))
    )
    (net (code "36") (name "/RESET") (class "Default")
      (node (ref "CON1") (pin "RESET") (pinfunction "RESET_RESET") (pintype "passive"))
      (node (ref "IC1") (pin "3") (pinfunction "/MR_3") (pintype "input"))
      (node (ref "R15") (pin "1") (pinfunction "1_1") (pintype "passive"))
      (node (ref "RESET1") (pin "2") (pinfunction "2_2") (pintype "passive"))
      (node (ref "U$4") (pin "13") (pinfunction "/RESET_13") (pintype "bidirectional"))
    )
    (net (code "37") (name "/RX") (class "Default")
      (node (ref "JP5") (pin "8") (pinfunction "8_8") (pintype "passive"))
      (node (ref "R10") (pin "2") (pinfunction "2_2") (pintype "passive"))
      (node (ref "U$4") (pin "20") (pinfunction "PD2(INT2/RXD1)_20") (pintype "bidirectional"))
    )
    (net (code "38") (name "/RXIN") (class "Default")
      (node (ref "ETHERNET") (pin "P$9") (pinfunction "RD-_P$9") (pintype "bidirectional"))
      (node (ref "IC2") (pin "6") (pinfunction "RXIN_6") (pintype "bidirectional"))
      (node (ref "R21") (pin "2") (pinfunction "2_2") (pintype "passive"))
    )
    (net (code "39") (name "/RXIP") (class "Default")
      (node (ref "ETHERNET") (pin "P$8") (pinfunction "RD+_P$8") (pintype "bidirectional"))
      (node (ref "IC2") (pin "5") (pinfunction "RXIP_5") (pintype "bidirectional"))
      (node (ref "R20") (pin "2") (pinfunction "2_2") (pintype "passive"))
    )
    (net (code "40") (name "/RXLED") (class "Default")
      (node (ref "RL5") (pin "1") (pinfunction "1_1") (pintype "passive"))
      (node (ref "U$4") (pin "8") (pinfunction "PB0(SS)_8") (pintype "bidirectional"))
    )
    (net (code "41") (name "/SCK") (class "Default")
      (node (ref "CON1") (pin "SCK") (pinfunction "SCK_SCK") (pintype "passive"))
      (node (ref "IC2") (pin "30") (pinfunction "SCLK_30") (pintype "bidirectional"))
      (node (ref "R18") (pin "1") (pinfunction "1_1") (pintype "passive"))
      (node (ref "U$4") (pin "9") (pinfunction "PB1(SCK)_9") (pintype "bidirectional"))
    )
    (net (code "42") (name "/SCL") (class "Default")
      (node (ref "JP5") (pin "6") (pinfunction "6_6") (pintype "passive"))
      (node (ref "R11") (pin "2") (pinfunction "2_2") (pintype "passive"))
      (node (ref "R12") (pin "1") (pinfunction "1_1") (pintype "passive"))
      (node (ref "U$4") (pin "18") (pinfunction "PD0(INT0/OC0B/SCL)_18") (pintype "bidirectional"))
    )
    (net (code "43") (name "/SDA") (class "Default")
      (node (ref "JP5") (pin "5") (pinfunction "5_5") (pintype "passive"))
      (node (ref "R14") (pin "1") (pinfunction "1_1") (pintype "passive"))
      (node (ref "R8") (pin "2") (pinfunction "2_2") (pintype "passive"))
      (node (ref "U$4") (pin "19") (pinfunction "PD1(INT1/SDA)_19") (pintype "bidirectional"))
    )
    (net (code "44") (name "/SEN") (class "Default")
      (node (ref "IC2") (pin "31") (pinfunction "SEN_31") (pintype "bidirectional"))
      (node (ref "Q3") (pin "3") (pinfunction "D_3") (pintype "passive"))
      (node (ref "R26") (pin "2") (pinfunction "2_2") (pintype "passive"))
    )
    (net (code "45") (name "/SPDLED") (class "Default")
      (node (ref "IC2") (pin "67") (pinfunction "SPDLED_67") (pintype "bidirectional"))
    )
    (net (code "46") (name "/SS") (class "Default")
      (node (ref "IC2") (pin "29") (pinfunction "/SCS_29") (pintype "bidirectional"))
      (node (ref "Q3") (pin "1") (pinfunction "G_1") (pintype "passive"))
      (node (ref "U$4") (pin "30") (pinfunction "PB6(OC1B/OC4B/ADC13)_30") (pintype "bidirectional"))
    )
    (net (code "47") (name "/TX") (class "Default")
      (node (ref "JP5") (pin "7") (pinfunction "7_7") (pintype "passive"))
      (node (ref "R9") (pin "2") (pinfunction "2_2") (pintype "passive"))
      (node (ref "U$4") (pin "21") (pinfunction "PD3(INT3/TXD1)_21") (pintype "bidirectional"))
    )
    (net (code "48") (name "/TXLED") (class "Default")
      (node (ref "RL6") (pin "1") (pinfunction "1_1") (pintype "passive"))
      (node (ref "U$4") (pin "22") (pinfunction "PD5(XCK/CTS)_22") (pintype "bidirectional"))
    )
    (net (code "49") (name "/TXON") (class "Default")
      (node (ref "ETHERNET") (pin "P$3") (pinfunction "TD-_P$3") (pintype "bidirectional"))
      (node (ref "IC2") (pin "9") (pinfunction "TXON_9") (pintype "bidirectional"))
      (node (ref "R23") (pin "2") (pinfunction "2_2") (pintype "passive"))
    )
    (net (code "50") (name "/TXOP") (class "Default")
      (node (ref "ETHERNET") (pin "P$2") (pinfunction "TD+_P$2") (pintype "bidirectional"))
      (node (ref "IC2") (pin "8") (pinfunction "TXOP_8") (pintype "bidirectional"))
      (node (ref "R22") (pin "2") (pinfunction "2_2") (pintype "passive"))
    )
    (net (code "51") (name "/WRXLED") (class "Default")
      (node (ref "IC2") (pin "72") (pinfunction "RXLED_72") (pintype "bidirectional"))
    )
    (net (code "52") (name "/WTXLED") (class "Default")
      (node (ref "IC2") (pin "73") (pinfunction "TXLED_73") (pintype "bidirectional"))
    )
    (net (code "53") (name "/XTAL1") (class "Default")
      (node (ref "C2") (pin "2") (pinfunction "2_2") (pintype "passive"))
      (node (ref "R13") (pin "1") (pinfunction "1_1") (pintype "passive"))
      (node (ref "U$4") (pin "16") (pinfunction "XTAL2_16") (pintype "bidirectional"))
      (node (ref "X3") (pin "P$1") (pinfunction "P$1_P$1") (pintype "bidirectional"))
    )
    (net (code "54") (name "/{slash}INT") (class "Default")
      (node (ref "IC2") (pin "56") (pinfunction "/INT_56") (pintype "bidirectional"))
      (node (ref "JP4") (pin "1") (pinfunction "1_1") (pintype "passive"))
    )
    (net (code "55") (name "/{slash}RESET") (class "Default")
      (node (ref "IC1") (pin "2") (pinfunction "/RESET_2") (pintype "output"))
      (node (ref "IC2") (pin "59") (pinfunction "/RESET_59") (pintype "bidirectional"))
    )
    (net (code "56") (name "3.3V") (class "Default")
      (node (ref "C25") (pin "1") (pinfunction "1_1") (pintype "passive"))
      (node (ref "C6") (pin "A") (pinfunction "+_A") (pintype "passive"))
      (node (ref "ETHERNET") (pin "P$11") (pinfunction "G+_P$11") (pintype "bidirectional"))
      (node (ref "ETHERNET") (pin "P$14") (pinfunction "Y+_P$14") (pintype "bidirectional"))
      (node (ref "IC2") (pin "12") (pinfunction "VCC3V3D0_12") (pintype "bidirectional"))
      (node (ref "IC2") (pin "18") (pinfunction "VCC3V3D1_18") (pintype "bidirectional"))
      (node (ref "IC2") (pin "44") (pinfunction "VCC3V3D2_44") (pintype "bidirectional"))
      (node (ref "IC3") (pin "3") (pinfunction "VOUT_3") (pintype "output"))
      (node (ref "JP5") (pin "3") (pinfunction "3_3") (pintype "passive"))
      (node (ref "R1") (pin "2") (pinfunction "2_2") (pintype "passive"))
      (node (ref "R16") (pin "2") (pinfunction "2_2") (pintype "passive"))
      (node (ref "R26") (pin "1") (pinfunction "1_1") (pintype "passive"))
      (node (ref "R27") (pin "2") (pinfunction "2_2") (pintype "passive"))
      (node (ref "R28") (pin "2") (pinfunction "2_2") (pintype "passive"))
      (node (ref "U$5") (pin "3") (pinfunction "WP_3") (pintype "bidirectional"))
      (node (ref "U$5") (pin "7") (pinfunction "HOLD_7") (pintype "bidirectional"))
      (node (ref "U$5") (pin "8") (pinfunction "VCC_8") (pintype "bidirectional"))
    )
    (net (code "57") (name "GND") (class "Default")
      (node (ref "C10") (pin "2") (pinfunction "2_2") (pintype "passive"))
      (node (ref "C11") (pin "2") (pinfunction "2_2") (pintype "passive"))
      (node (ref "C12") (pin "1") (pinfunction "1_1") (pintype "passive"))
      (node (ref "C14") (pin "2") (pinfunction "2_2") (pintype "passive"))
      (node (ref "C15") (pin "2") (pinfunction "2_2") (pintype "passive"))
      (node (ref "C2") (pin "1") (pinfunction "1_1") (pintype "passive"))
      (node (ref "C22") (pin "2") (pinfunction "2_2") (pintype "passive"))
      (node (ref "C23") (pin "2") (pinfunction "2_2") (pintype "passive"))
      (node (ref "C24") (pin "2") (pinfunction "2_2") (pintype "passive"))
      (node (ref "C25") (pin "2") (pinfunction "2_2") (pintype "passive"))
      (node (ref "C26") (pin "2") (pinfunction "2_2") (pintype "passive"))
      (node (ref "C3") (pin "1") (pinfunction "1_1") (pintype "passive"))
      (node (ref "C31") (pin "2") (pinfunction "2_2") (pintype "passive"))
      (node (ref "C32") (pin "2") (pinfunction "2_2") (pintype "passive"))
      (node (ref "C34") (pin "2") (pinfunction "2_2") (pintype "passive"))
      (node (ref "C35") (pin "2") (pinfunction "2_2") (pintype "passive"))
      (node (ref "C36") (pin "2") (pinfunction "2_2") (pintype "passive"))
      (node (ref "C37") (pin "2") (pinfunction "2_2") (pintype "passive"))
      (node (ref "C4") (pin "1") (pinfunction "1_1") (pintype "passive"))
      (node (ref "C5") (pin "2") (pinfunction "2_2") (pintype "passive"))
      (node (ref "C6") (pin "C") (pinfunction "-_C") (pintype "passive"))
      (node (ref "C7") (pin "1") (pinfunction "1_1") (pintype "passive"))
      (node (ref "C8") (pin "1") (pinfunction "1_1") (pintype "passive"))
      (node (ref "CON1") (pin "GND") (pinfunction "GND_GND") (pintype "passive"))
      (node (ref "ETHERNET") (pin "GND1") (pinfunction "GND1_GND1") (pintype "bidirectional"))
      (node (ref "ETHERNET") (pin "GND2") (pinfunction "GND2_GND2") (pintype "bidirectional"))
      (node (ref "ETHERNET") (pin "P$5") (pinfunction "P4_P$5") (pintype "bidirectional"))
      (node (ref "ETHERNET") (pin "P$6") (pinfunction "GND_P$6") (pintype "bidirectional"))
      (node (ref "FDX") (pin "2") (pinfunction "C_2") (pintype "passive"))
      (node (ref "I2C_INT0") (pin "GND1") (pinfunction "6_GND1") (pintype "power_in"))
      (node (ref "I2C_INT0") (pin "GND2") (pinfunction "4_GND2") (pintype "power_in"))
      (node (ref "IC1") (pin "1") (pinfunction "GND_1") (pintype "power_in"))
      (node (ref "IC2") (pin "10") (pinfunction "GNDA1_10") (pintype "bidirectional"))
      (node (ref "IC2") (pin "13") (pinfunction "GNDD0_13") (pintype "bidirectional"))
      (node (ref "IC2") (pin "14") (pinfunction "GNDD1_14") (pintype "bidirectional"))
      (node (ref "IC2") (pin "17") (pinfunction "GNDD2_17") (pintype "bidirectional"))
      (node (ref "IC2") (pin "19") (pinfunction "DATA7_19") (pintype "bidirectional"))
      (node (ref "IC2") (pin "20") (pinfunction "DATA6_20") (pintype "bidirectional"))
      (node (ref "IC2") (pin "21") (pinfunction "DATA5_21") (pintype "bidirectional"))
      (node (ref "IC2") (pin "22") (pinfunction "DATA4_22") (pintype "bidirectional"))
      (node (ref "IC2") (pin "23") (pinfunction "DATA3_23") (pintype "bidirectional"))
      (node (ref "IC2") (pin "24") (pinfunction "DATA2_24") (pintype "bidirectional"))
      (node (ref "IC2") (pin "25") (pinfunction "DATA1_25") (pintype "bidirectional"))
      (node (ref "IC2") (pin "26") (pinfunction "DATA0_26") (pintype "bidirectional"))
      (node (ref "IC2") (pin "32") (pinfunction "GNDD3_32") (pintype "bidirectional"))
      (node (ref "IC2") (pin "34") (pinfunction "TEST_MODE3_34") (pintype "bidirectional"))
      (node (ref "IC2") (pin "35") (pinfunction "TEST_MODE2_35") (pintype "bidirectional"))
      (node (ref "IC2") (pin "36") (pinfunction "TEST_MODE1_36") (pintype "bidirectional"))
      (node (ref "IC2") (pin "37") (pinfunction "TEST_MODE0_37") (pintype "bidirectional"))
      (node (ref "IC2") (pin "38") (pinfunction "ADDR14_38") (pintype "bidirectional"))
      (node (ref "IC2") (pin "39") (pinfunction "ADDR13_39") (pintype "bidirectional"))
      (node (ref "IC2") (pin "4") (pinfunction "GNDA0_4") (pintype "bidirectional"))
      (node (ref "IC2") (pin "40") (pinfunction "ADDR12_40") (pintype "bidirectional"))
      (node (ref "IC2") (pin "41") (pinfunction "ADDR11_41") (pintype "bidirectional"))
      (node (ref "IC2") (pin "42") (pinfunction "ADDR10_42") (pintype "bidirectional"))
      (node (ref "IC2") (pin "43") (pinfunction "GNDD4_43") (pintype "bidirectional"))
      (node (ref "IC2") (pin "45") (pinfunction "ADDR9_45") (pintype "bidirectional"))
      (node (ref "IC2") (pin "46") (pinfunction "ADDR8_46") (pintype "bidirectional"))
      (node (ref "IC2") (pin "47") (pinfunction "ADDR7_47") (pintype "bidirectional"))
      (node (ref "IC2") (pin "48") (pinfunction "ADDR6_48") (pintype "bidirectional"))
      (node (ref "IC2") (pin "49") (pinfunction "ADDR5_49") (pintype "bidirectional"))
      (node (ref "IC2") (pin "50") (pinfunction "ADDR4_50") (pintype "bidirectional"))
      (node (ref "IC2") (pin "51") (pinfunction "ADDR3_51") (pintype "bidirectional"))
      (node (ref "IC2") (pin "52") (pinfunction "ADDR2_52") (pintype "bidirectional"))
      (node (ref "IC2") (pin "53") (pinfunction "ADDR1_53") (pintype "bidirectional"))
      (node (ref "IC2") (pin "54") (pinfunction "ADDR0_54") (pintype "bidirectional"))
      (node (ref "IC2") (pin "63") (pinfunction "OPMODE0_63") (pintype "bidirectional"))
      (node (ref "IC2") (pin "64") (pinfunction "OPMODE1_64") (pintype "bidirectional"))
      (node (ref "IC2") (pin "65") (pinfunction "OPMODE2_65") (pintype "bidirectional"))
      (node (ref "IC2") (pin "68") (pinfunction "GNDD5_68") (pintype "bidirectional"))
      (node (ref "IC2") (pin "77") (pinfunction "GNDA2_77") (pintype "bidirectional"))
      (node (ref "IC3") (pin "2") (pinfunction "GND_2") (pintype "power_in"))
      (node (ref "J1") (pin "GND1") (pinfunction "6_GND1") (pintype "power_in"))
      (node (ref "J1") (pin "GND2") (pinfunction "4_GND2") (pintype "power_in"))
      (node (ref "J2") (pin "GND1") (pinfunction "6_GND1") (pintype "power_in"))
      (node (ref "J2") (pin "GND2") (pinfunction "4_GND2") (pintype "power_in"))
      (node (ref "J3") (pin "GND1") (pinfunction "6_GND1") (pintype "power_in"))
      (node (ref "J3") (pin "GND2") (pinfunction "4_GND2") (pintype "power_in"))
      (node (ref "J4") (pin "GND1") (pinfunction "6_GND1") (pintype "power_in"))
      (node (ref "J4") (pin "GND2") (pinfunction "4_GND2") (pintype "power_in"))
      (node (ref "J5") (pin "GND1") (pinfunction "6_GND1") (pintype "power_in"))
      (node (ref "J5") (pin "GND2") (pinfunction "4_GND2") (pintype "power_in"))
      (node (ref "J7") (pin "GND1") (pinfunction "6_GND1") (pintype "power_in"))
      (node (ref "J7") (pin "GND2") (pinfunction "4_GND2") (pintype "power_in"))
      (node (ref "JP5") (pin "4") (pinfunction "4_4") (pintype "passive"))
      (node (ref "LED10") (pin "K") (pinfunction "C_K") (pintype "passive"))
      (node (ref "LED14") (pin "K") (pinfunction "C_K") (pintype "passive"))
      (node (ref "LED3") (pin "K") (pinfunction "C_K") (pintype "passive"))
      (node (ref "LED4") (pin "K") (pinfunction "C_K") (pintype "passive"))
      (node (ref "LED9") (pin "K") (pinfunction "C_K") (pintype "passive"))
      (node (ref "Q1") (pin "2") (pinfunction "D_2") (pintype "passive"))
      (node (ref "Q2") (pin "2") (pinfunction "D_2") (pintype "passive"))
      (node (ref "Q3") (pin "2") (pinfunction "S_2") (pintype "passive"))
      (node (ref "Q4") (pin "2") (pinfunction "D_2") (pintype "passive"))
      (node (ref "Q5") (pin "2") (pinfunction "D_2") (pintype "passive"))
      (node (ref "Q6") (pin "2") (pinfunction "D_2") (pintype "passive"))
      (node (ref "R3") (pin "1") (pinfunction "1_1") (pintype "passive"))
      (node (ref "R30") (pin "1") (pinfunction "1_1") (pintype "passive"))
      (node (ref "RESET1") (pin "4") (pinfunction "4_4") (pintype "passive"))
      (node (ref "SERIAL") (pin "2") (pinfunction "C_2") (pintype "passive"))
      (node (ref "SG1") (pin "-") (pinfunction "2_-") (pintype "passive"))
      (node (ref "U$4") (pin "15") (pinfunction "GND_15") (pintype "bidirectional"))
      (node (ref "U$4") (pin "23") (pinfunction "GND1_23") (pintype "bidirectional"))
      (node (ref "U$4") (pin "35") (pinfunction "GND2_35") (pintype "bidirectional"))
      (node (ref "U$4") (pin "43") (pinfunction "GND3_43") (pintype "bidirectional"))
      (node (ref "U$4") (pin "5") (pinfunction "UGND_5") (pintype "bidirectional"))
      (node (ref "U$5") (pin "4") (pinfunction "GND_4") (pintype "bidirectional"))
      (node (ref "U$6") (pin "GND1") (pinfunction "GND1_GND1") (pintype "input"))
      (node (ref "U$6") (pin "GND2") (pinfunction "GND2_GND2") (pintype "input"))
      (node (ref "USB") (pin "2") (pinfunction "C_2") (pintype "passive"))
      (node (ref "X4") (pin "5") (pinfunction "5_5") (pintype "input"))
    )
    (net (code "58") (name "Net-(C23-Pad1)") (class "Default")
      (node (ref "C23") (pin "1") (pinfunction "1_1") (pintype "passive"))
      (node (ref "R20") (pin "1") (pinfunction "1_1") (pintype "passive"))
      (node (ref "R21") (pin "1") (pinfunction "1_1") (pintype "passive"))
    )
    (net (code "59") (name "Net-(C24-Pad1)") (class "Default")
      (node (ref "C24") (pin "1") (pinfunction "1_1") (pintype "passive"))
      (node (ref "R22") (pin "1") (pinfunction "1_1") (pintype "passive"))
      (node (ref "R23") (pin "1") (pinfunction "1_1") (pintype "passive"))
    )
    (net (code "60") (name "Net-(ETHERNET-G-)") (class "Default")
      (node (ref "ETHERNET") (pin "P$12") (pinfunction "G-_P$12") (pintype "bidirectional"))
      (node (ref "R2") (pin "1") (pinfunction "1_1") (pintype "passive"))
    )
    (net (code "61") (name "Net-(ETHERNET-Y-)") (class "Default")
      (node (ref "ETHERNET") (pin "P$13") (pinfunction "Y-_P$13") (pintype "bidirectional"))
      (node (ref "R19") (pin "1") (pinfunction "1_1") (pintype "passive"))
    )
    (net (code "62") (name "Net-(F1-Pad1)") (class "Default")
      (node (ref "F1") (pin "1") (pinfunction "1_1") (pintype "passive"))
      (node (ref "U$6") (pin "+12V") (pinfunction "+12V_+12V") (pintype "power_in"))
    )
    (net (code "63") (name "Net-(F2-Pad1)") (class "Default")
      (node (ref "F2") (pin "1") (pinfunction "1_1") (pintype "passive"))
      (node (ref "U$6") (pin "+5V") (pinfunction "+5V_+5V") (pintype "power_in"))
    )
    (net (code "64") (name "Net-(FDX-AG)") (class "Default")
      (node (ref "FDX") (pin "1") (pinfunction "AG_1") (pintype "passive"))
      (node (ref "RL9") (pin "2") (pinfunction "2_2") (pintype "passive"))
    )
    (net (code "65") (name "Net-(FDX-AR)") (class "Default")
      (node (ref "FDX") (pin "3") (pinfunction "AR_3") (pintype "passive"))
      (node (ref "RL8") (pin "2") (pinfunction "2_2") (pintype "passive"))
    )
    (net (code "66") (name "Net-(I2C_INT0-2)") (class "Default")
      (node (ref "I2C_INT0") (pin "SCL") (pinfunction "2_SCL") (pintype "bidirectional"))
      (node (ref "R11") (pin "1") (pinfunction "1_1") (pintype "passive"))
    )
    (net (code "67") (name "Net-(I2C_INT0-3)") (class "Default")
      (node (ref "I2C_INT0") (pin "SDA") (pinfunction "3_SDA") (pintype "bidirectional"))
      (node (ref "R8") (pin "1") (pinfunction "1_1") (pintype "passive"))
    )
    (net (code "68") (name "Net-(IC2-RSET_BG)") (class "Default")
      (node (ref "IC2") (pin "1") (pinfunction "RSET_BG_1") (pintype "bidirectional"))
      (node (ref "R30") (pin "2") (pinfunction "2_2") (pintype "passive"))
    )
    (net (code "69") (name "Net-(IC2-XTLN)") (class "Default")
      (node (ref "C31") (pin "1") (pinfunction "1_1") (pintype "passive"))
      (node (ref "IC2") (pin "75") (pinfunction "XTLN_75") (pintype "bidirectional"))
      (node (ref "R29") (pin "2") (pinfunction "2_2") (pintype "passive"))
      (node (ref "X1") (pin "P$2") (pinfunction "P$2_P$2") (pintype "bidirectional"))
    )
    (net (code "70") (name "Net-(IC2-XTLP)") (class "Default")
      (node (ref "C22") (pin "1") (pinfunction "1_1") (pintype "passive"))
      (node (ref "IC2") (pin "76") (pinfunction "XTLP_76") (pintype "bidirectional"))
      (node (ref "R29") (pin "1") (pinfunction "1_1") (pintype "passive"))
      (node (ref "X1") (pin "P$1") (pinfunction "P$1_P$1") (pintype "bidirectional"))
    )
    (net (code "71") (name "Net-(IC2-{slash}CS)") (class "Default")
      (node (ref "IC2") (pin "55") (pinfunction "/CS_55") (pintype "bidirectional"))
      (node (ref "IC2") (pin "57") (pinfunction "/WR_57") (pintype "bidirectional"))
      (node (ref "IC2") (pin "58") (pinfunction "/RD_58") (pintype "bidirectional"))
      (node (ref "R28") (pin "1") (pinfunction "1_1") (pintype "passive"))
    )
    (net (code "72") (name "Net-(J1-2)") (class "Default")
      (node (ref "J1") (pin "PWM") (pinfunction "2_PWM") (pintype "bidirectional"))
      (node (ref "LED5") (pin "K") (pinfunction "C_K") (pintype "passive"))
      (node (ref "Q2") (pin "3") (pinfunction "S_3") (pintype "passive"))
    )
    (net (code "73") (name "Net-(J1-3)") (class "Default")
      (node (ref "J1") (pin "I/O") (pinfunction "3_I/O") (pintype "bidirectional"))
      (node (ref "R32") (pin "2") (pinfunction "2_2") (pintype "passive"))
    )
    (net (code "74") (name "Net-(J2-2)") (class "Default")
      (node (ref "J2") (pin "PWM") (pinfunction "2_PWM") (pintype "bidirectional"))
      (node (ref "LED6") (pin "K") (pinfunction "C_K") (pintype "passive"))
      (node (ref "Q4") (pin "3") (pinfunction "S_3") (pintype "passive"))
    )
    (net (code "75") (name "Net-(J2-3)") (class "Default")
      (node (ref "J2") (pin "I/O") (pinfunction "3_I/O") (pintype "bidirectional"))
      (node (ref "R33") (pin "2") (pinfunction "2_2") (pintype "passive"))
    )
    (net (code "76") (name "Net-(J3-2)") (class "Default")
      (node (ref "J3") (pin "PWM") (pinfunction "2_PWM") (pintype "bidirectional"))
      (node (ref "LED7") (pin "K") (pinfunction "C_K") (pintype "passive"))
      (node (ref "Q5") (pin "3") (pinfunction "S_3") (pintype "passive"))
    )
    (net (code "77") (name "Net-(J3-3)") (class "Default")
      (node (ref "J3") (pin "I/O") (pinfunction "3_I/O") (pintype "bidirectional"))
      (node (ref "R34") (pin "2") (pinfunction "2_2") (pintype "passive"))
    )
    (net (code "78") (name "Net-(J4-2)") (class "Default")
      (node (ref "J4") (pin "PWM") (pinfunction "2_PWM") (pintype "bidirectional"))
      (node (ref "LED8") (pin "K") (pinfunction "C_K") (pintype "passive"))
      (node (ref "Q6") (pin "3") (pinfunction "S_3") (pintype "passive"))
    )
    (net (code "79") (name "Net-(J4-3)") (class "Default")
      (node (ref "J4") (pin "I/O") (pinfunction "3_I/O") (pintype "bidirectional"))
      (node (ref "R35") (pin "2") (pinfunction "2_2") (pintype "passive"))
    )
    (net (code "80") (name "Net-(J5-2)") (class "Default")
      (node (ref "J5") (pin "RX") (pinfunction "2_RX") (pintype "bidirectional"))
      (node (ref "R10") (pin "1") (pinfunction "1_1") (pintype "passive"))
    )
    (net (code "81") (name "Net-(J5-3)") (class "Default")
      (node (ref "J5") (pin "TX") (pinfunction "3_TX") (pintype "bidirectional"))
      (node (ref "R9") (pin "1") (pinfunction "1_1") (pintype "passive"))
    )
    (net (code "82") (name "Net-(J7-2)") (class "Default")
      (node (ref "J7") (pin "PWM") (pinfunction "2_PWM") (pintype "bidirectional"))
      (node (ref "LED2") (pin "K") (pinfunction "C_K") (pintype "passive"))
      (node (ref "Q1") (pin "3") (pinfunction "S_3") (pintype "passive"))
    )
    (net (code "83") (name "Net-(J7-3)") (class "Default")
      (node (ref "J7") (pin "I/O") (pinfunction "3_I/O") (pintype "bidirectional"))
      (node (ref "R") (pin "2") (pinfunction "2_2") (pintype "passive"))
    )
    (net (code "84") (name "Net-(LED2-PadA)") (class "Default")
      (node (ref "LED2") (pin "A") (pinfunction "A_A") (pintype "passive"))
      (node (ref "R25") (pin "1") (pinfunction "1_1") (pintype "passive"))
    )
    (net (code "85") (name "Net-(LED3-PadA)") (class "Default")
      (node (ref "LED3") (pin "A") (pinfunction "A_A") (pintype "passive"))
      (node (ref "R27") (pin "1") (pinfunction "1_1") (pintype "passive"))
    )
    (net (code "86") (name "Net-(LED4-PadA)") (class "Default")
      (node (ref "LED4") (pin "A") (pinfunction "A_A") (pintype "passive"))
      (node (ref "RL4") (pin "2") (pinfunction "2_2") (pintype "passive"))
    )
    (net (code "87") (name "Net-(LED5-PadA)") (class "Default")
      (node (ref "LED5") (pin "A") (pinfunction "A_A") (pintype "passive"))
      (node (ref "R4") (pin "1") (pinfunction "1_1") (pintype "passive"))
    )
    (net (code "88") (name "Net-(LED6-PadA)") (class "Default")
      (node (ref "LED6") (pin "A") (pinfunction "A_A") (pintype "passive"))
      (node (ref "R5") (pin "1") (pinfunction "1_1") (pintype "passive"))
    )
    (net (code "89") (name "Net-(LED7-PadA)") (class "Default")
      (node (ref "LED7") (pin "A") (pinfunction "A_A") (pintype "passive"))
      (node (ref "R6") (pin "1") (pinfunction "1_1") (pintype "passive"))
    )
    (net (code "90") (name "Net-(LED8-PadA)") (class "Default")
      (node (ref "LED8") (pin "A") (pinfunction "A_A") (pintype "passive"))
      (node (ref "R7") (pin "1") (pinfunction "1_1") (pintype "passive"))
    )
    (net (code "91") (name "Net-(LED9-PadA)") (class "Default")
      (node (ref "LED9") (pin "A") (pinfunction "A_A") (pintype "passive"))
      (node (ref "RL2") (pin "1") (pinfunction "1_1") (pintype "passive"))
    )
    (net (code "92") (name "Net-(LED10-PadA)") (class "Default")
      (node (ref "LED10") (pin "A") (pinfunction "A_A") (pintype "passive"))
      (node (ref "RL3") (pin "1") (pinfunction "1_1") (pintype "passive"))
    )
    (net (code "93") (name "Net-(LED14-PadA)") (class "Default")
      (node (ref "LED14") (pin "A") (pinfunction "A_A") (pintype "passive"))
      (node (ref "RL11") (pin "2") (pinfunction "2_2") (pintype "passive"))
    )
    (net (code "94") (name "Net-(R24-Pad2)") (class "Default")
      (node (ref "R24") (pin "2") (pinfunction "2_2") (pintype "passive"))
      (node (ref "X4") (pin "3") (pinfunction "3_3") (pintype "input"))
    )
    (net (code "95") (name "Net-(R31-Pad2)") (class "Default")
      (node (ref "R31") (pin "2") (pinfunction "2_2") (pintype "passive"))
      (node (ref "X4") (pin "2") (pinfunction "2_2") (pintype "input"))
    )
    (net (code "96") (name "Net-(SERIAL-AG)") (class "Default")
      (node (ref "RL6") (pin "2") (pinfunction "2_2") (pintype "passive"))
      (node (ref "SERIAL") (pin "1") (pinfunction "AG_1") (pintype "passive"))
    )
    (net (code "97") (name "Net-(SERIAL-AR)") (class "Default")
      (node (ref "RL5") (pin "2") (pinfunction "2_2") (pintype "passive"))
      (node (ref "SERIAL") (pin "3") (pinfunction "AR_3") (pintype "passive"))
    )
    (net (code "98") (name "Net-(U$4-AVCC)") (class "Default")
      (node (ref "C1") (pin "2") (pinfunction "2_2") (pintype "passive"))
      (node (ref "U$4") (pin "24") (pinfunction "AVCC_24") (pintype "bidirectional"))
      (node (ref "U$4") (pin "44") (pinfunction "AVCC1_44") (pintype "bidirectional"))
    )
    (net (code "99") (name "Net-(U$4-UCAP)") (class "Default")
      (node (ref "C3") (pin "2") (pinfunction "2_2") (pintype "passive"))
      (node (ref "U$4") (pin "6") (pinfunction "UCAP_6") (pintype "bidirectional"))
    )
    (net (code "100") (name "Net-(U$5-CS)") (class "Default")
      (node (ref "R16") (pin "1") (pinfunction "1_1") (pintype "passive"))
      (node (ref "R17") (pin "1") (pinfunction "1_1") (pintype "passive"))
      (node (ref "U$5") (pin "1") (pinfunction "CS_1") (pintype "bidirectional"))
    )
    (net (code "101") (name "Net-(U$5-SCK)") (class "Default")
      (node (ref "R18") (pin "2") (pinfunction "2_2") (pintype "passive"))
      (node (ref "U$5") (pin "6") (pinfunction "SCK_6") (pintype "bidirectional"))
    )
    (net (code "102") (name "Net-(USB-AG)") (class "Default")
      (node (ref "RL7") (pin "2") (pinfunction "2_2") (pintype "passive"))
      (node (ref "USB") (pin "1") (pinfunction "AG_1") (pintype "passive"))
    )
    (net (code "103") (name "Net-(USB-AR)") (class "Default")
      (node (ref "RL1") (pin "2") (pinfunction "2_2") (pintype "passive"))
      (node (ref "USB") (pin "3") (pinfunction "AR_3") (pintype "passive"))
    )
    (net (code "104") (name "VUSB") (class "Default")
      (node (ref "C7") (pin "2") (pinfunction "2_2") (pintype "passive"))
      (node (ref "D4") (pin "A") (pinfunction "A_A") (pintype "passive"))
      (node (ref "U$4") (pin "2") (pinfunction "UVCC_2") (pintype "bidirectional"))
      (node (ref "U$4") (pin "7") (pinfunction "VBUS_7") (pintype "bidirectional"))
      (node (ref "X4") (pin "1") (pinfunction "1_1") (pintype "input"))
    )
    (net (code "105") (name "unconnected-(IC2-NC0-Pad3)") (class "Default")
      (node (ref "IC2") (pin "3") (pinfunction "NC0_3") (pintype "bidirectional"))
    )
    (net (code "106") (name "unconnected-(IC2-NC1-Pad60)") (class "Default")
      (node (ref "IC2") (pin "60") (pinfunction "NC1_60") (pintype "bidirectional"))
    )
    (net (code "107") (name "unconnected-(IC2-NC2-Pad61)") (class "Default")
      (node (ref "IC2") (pin "61") (pinfunction "NC2_61") (pintype "bidirectional"))
    )
    (net (code "108") (name "unconnected-(IC2-NC3-Pad62)") (class "Default")
      (node (ref "IC2") (pin "62") (pinfunction "NC3_62") (pintype "bidirectional"))
    )
    (net (code "109") (name "unconnected-(IC2-NC4-Pad78)") (class "Default")
      (node (ref "IC2") (pin "78") (pinfunction "NC4_78") (pintype "bidirectional"))
    )
    (net (code "110") (name "unconnected-(IC2-NC5-Pad79)") (class "Default")
      (node (ref "IC2") (pin "79") (pinfunction "NC5_79") (pintype "bidirectional"))
    )
    (net (code "111") (name "unconnected-(IC2-NC6-Pad80)") (class "Default")
      (node (ref "IC2") (pin "80") (pinfunction "NC6_80") (pintype "bidirectional"))
    )
    (net (code "112") (name "unconnected-(L2-Pad1)") (class "Default")
      (node (ref "L2") (pin "1") (pinfunction "1_1") (pintype "passive"))
    )
    (net (code "113") (name "unconnected-(Q1-D-Pad4)") (class "Default")
      (node (ref "Q1") (pin "4") (pinfunction "D_4") (pintype "passive"))
    )
    (net (code "114") (name "unconnected-(Q2-D-Pad4)") (class "Default")
      (node (ref "Q2") (pin "4") (pinfunction "D_4") (pintype "passive"))
    )
    (net (code "115") (name "unconnected-(Q4-D-Pad4)") (class "Default")
      (node (ref "Q4") (pin "4") (pinfunction "D_4") (pintype "passive"))
    )
    (net (code "116") (name "unconnected-(Q5-D-Pad4)") (class "Default")
      (node (ref "Q5") (pin "4") (pinfunction "D_4") (pintype "passive"))
    )
    (net (code "117") (name "unconnected-(Q6-D-Pad4)") (class "Default")
      (node (ref "Q6") (pin "4") (pinfunction "D_4") (pintype "passive"))
    )
    (net (code "118") (name "unconnected-(RESET1-Pad1)") (class "Default")
      (node (ref "RESET1") (pin "1") (pinfunction "1_1") (pintype "passive"))
    )
    (net (code "119") (name "unconnected-(RESET1-Pad3)") (class "Default")
      (node (ref "RESET1") (pin "3") (pinfunction "3_3") (pintype "passive"))
    )
    (net (code "120") (name "unconnected-(X4-Pad4)") (class "Default")
      (node (ref "X4") (pin "4") (pinfunction "4_4") (pintype "input"))
    )
  )
)
